# Top_Screw.net
KiCad netlist of a schematic drawn in EAGLE
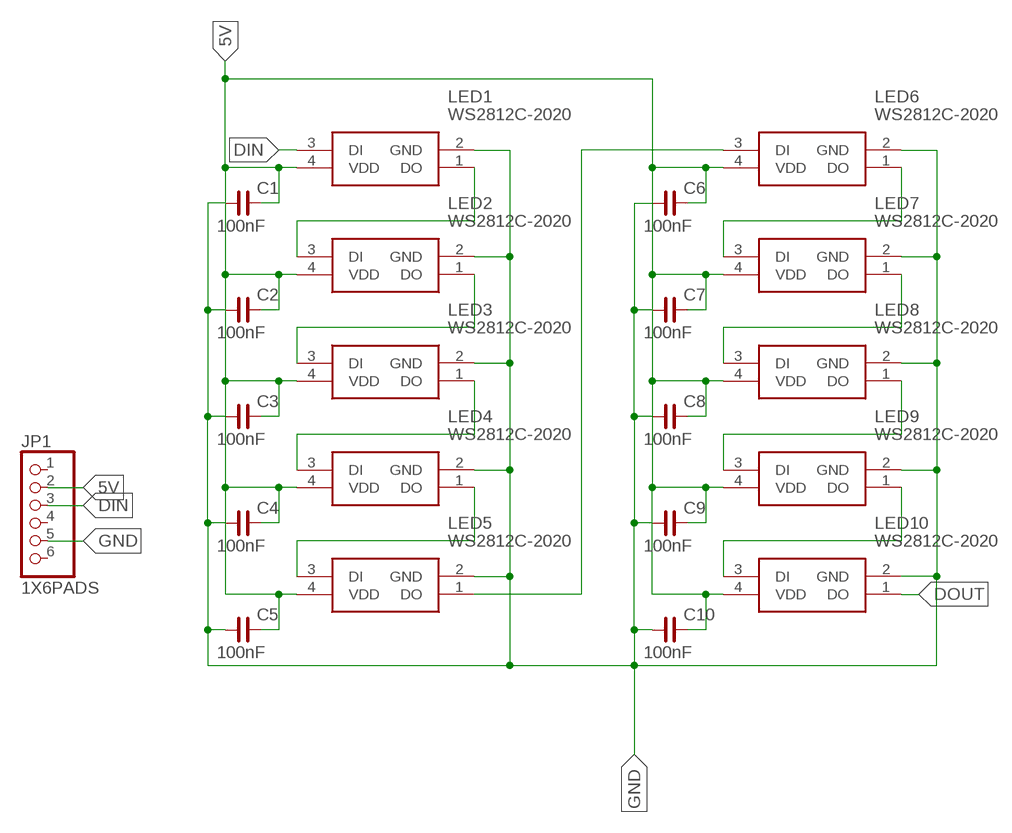
[diagram p0: schematic, sheet 1]

(export (version "E")
  (design (tool "Eeschema 10.0.6"))
  (components
    (comp (ref "C1")
      (value "100nF")
      (footprint "eagle-import:C0402")
      (libsource (lib "eagle-import") (part "C_0402"))
    )
    (comp (ref "C2")
      (value "100nF")
      (footprint "eagle-import:C0402")
      (libsource (lib "eagle-import") (part "C_0402"))
    )
    (comp (ref "C3")
      (value "100nF")
      (footprint "eagle-import:C0402")
      (libsource (lib "eagle-import") (part "C_0402"))
    )
    (comp (ref "C4")
      (value "100nF")
      (footprint "eagle-import:C0402")
      (libsource (lib "eagle-import") (part "C_0402"))
    )
    (comp (ref "C5")
      (value "100nF")
      (footprint "eagle-import:C0402")
      (libsource (lib "eagle-import") (part "C_0402"))
    )
    (comp (ref "C6")
      (value "100nF")
      (footprint "eagle-import:C0402")
      (libsource (lib "eagle-import") (part "C_0402"))
    )
    (comp (ref "C7")
      (value "100nF")
      (footprint "eagle-import:C0402")
      (libsource (lib "eagle-import") (part "C_0402"))
    )
    (comp (ref "C8")
      (value "100nF")
      (footprint "eagle-import:C0402")
      (libsource (lib "eagle-import") (part "C_0402"))
    )
    (comp (ref "C9")
      (value "100nF")
      (footprint "eagle-import:C0402")
      (libsource (lib "eagle-import") (part "C_0402"))
    )
    (comp (ref "C10")
      (value "100nF")
      (footprint "eagle-import:C0402")
      (libsource (lib "eagle-import") (part "C_0402"))
    )
    (comp (ref "JP1")
      (value "1X6PADS")
      (footprint "eagle-import:1X6PADS")
      (libsource (lib "eagle-import") (part "1X6PADS"))
    )
    (comp (ref "LED1")
      (value "WS2812C-2020")
      (footprint "eagle-import:WS2812C2020")
      (libsource (lib "eagle-import") (part "WS2812C-2020"))
    )
    (comp (ref "LED2")
      (value "WS2812C-2020")
      (footprint "eagle-import:WS2812C2020")
      (libsource (lib "eagle-import") (part "WS2812C-2020"))
    )
    (comp (ref "LED3")
      (value "WS2812C-2020")
      (footprint "eagle-import:WS2812C2020")
      (libsource (lib "eagle-import") (part "WS2812C-2020"))
    )
    (comp (ref "LED4")
      (value "WS2812C-2020")
      (footprint "eagle-import:WS2812C2020")
      (libsource (lib "eagle-import") (part "WS2812C-2020"))
    )
    (comp (ref "LED5")
      (value "WS2812C-2020")
      (footprint "eagle-import:WS2812C2020")
      (libsource (lib "eagle-import") (part "WS2812C-2020"))
    )
    (comp (ref "LED6")
      (value "WS2812C-2020")
      (footprint "eagle-import:WS2812C2020")
      (libsource (lib "eagle-import") (part "WS2812C-2020"))
    )
    (comp (ref "LED7")
      (value "WS2812C-2020")
      (footprint "eagle-import:WS2812C2020")
      (libsource (lib "eagle-import") (part "WS2812C-2020"))
    )
    (comp (ref "LED8")
      (value "WS2812C-2020")
      (footprint "eagle-import:WS2812C2020")
      (libsource (lib "eagle-import") (part "WS2812C-2020"))
    )
    (comp (ref "LED9")
      (value "WS2812C-2020")
      (footprint "eagle-import:WS2812C2020")
      (libsource (lib "eagle-import") (part "WS2812C-2020"))
    )
    (comp (ref "LED10")
      (value "WS2812C-2020")
      (footprint "eagle-import:WS2812C2020")
      (libsource (lib "eagle-import") (part "WS2812C-2020"))
    )
  )
  (nets
    (net (code "1") (name "5V") (class "Default")
      (node (ref "C1") (pin "2") (pinfunction "2_2") (pintype "passive"))
      (node (ref "C10") (pin "2") (pinfunction "2_2") (pintype "passive"))
      (node (ref "C2") (pin "2") (pinfunction "2_2") (pintype "passive"))
      (node (ref "C3") (pin "2") (pinfunction "2_2") (pintype "passive"))
      (node (ref "C4") (pin "2") (pinfunction "2_2") (pintype "passive"))
      (node (ref "C5") (pin "2") (pinfunction "2_2") (pintype "passive"))
      (node (ref "C6") (pin "2") (pinfunction "2_2") (pintype "passive"))
      (node (ref "C7") (pin "2") (pinfunction "2_2") (pintype "passive"))
      (node (ref "C8") (pin "2") (pinfunction "2_2") (pintype "passive"))
      (node (ref "C9") (pin "2") (pinfunction "2_2") (pintype "passive"))
      (node (ref "JP1") (pin "2") (pinfunction "2_2") (pintype "passive"))
      (node (ref "LED1") (pin "4") (pinfunction "VDD_4") (pintype "bidirectional"))
      (node (ref "LED10") (pin "4") (pinfunction "VDD_4") (pintype "bidirectional"))
      (node (ref "LED2") (pin "4") (pinfunction "VDD_4") (pintype "bidirectional"))
      (node (ref "LED3") (pin "4") (pinfunction "VDD_4") (pintype "bidirectional"))
      (node (ref "LED4") (pin "4") (pinfunction "VDD_4") (pintype "bidirectional"))
      (node (ref "LED5") (pin "4") (pinfunction "VDD_4") (pintype "bidirectional"))
      (node (ref "LED6") (pin "4") (pinfunction "VDD_4") (pintype "bidirectional"))
      (node (ref "LED7") (pin "4") (pinfunction "VDD_4") (pintype "bidirectional"))
      (node (ref "LED8") (pin "4") (pinfunction "VDD_4") (pintype "bidirectional"))
      (node (ref "LED9") (pin "4") (pinfunction "VDD_4") (pintype "bidirectional"))
    )
    (net (code "2") (name "DIN") (class "Default")
      (node (ref "JP1") (pin "3") (pinfunction "3_3") (pintype "passive"))
      (node (ref "LED1") (pin "3") (pinfunction "DI_3") (pintype "bidirectional"))
    )
    (net (code "3") (name "DOUT") (class "Default")
      (node (ref "LED10") (pin "1") (pinfunction "DO_1") (pintype "bidirectional"))
    )
    (net (code "4") (name "GND") (class "Default")
      (node (ref "C1") (pin "1") (pinfunction "1_1") (pintype "passive"))
      (node (ref "C10") (pin "1") (pinfunction "1_1") (pintype "passive"))
      (node (ref "C2") (pin "1") (pinfunction "1_1") (pintype "passive"))
      (node (ref "C3") (pin "1") (pinfunction "1_1") (pintype "passive"))
      (node (ref "C4") (pin "1") (pinfunction "1_1") (pintype "passive"))
      (node (ref "C5") (pin "1") (pinfunction "1_1") (pintype "passive"))
      (node (ref "C6") (pin "1") (pinfunction "1_1") (pintype "passive"))
      (node (ref "C7") (pin "1") (pinfunction "1_1") (pintype "passive"))
      (node (ref "C8") (pin "1") (pinfunction "1_1") (pintype "passive"))
      (node (ref "C9") (pin "1") (pinfunction "1_1") (pintype "passive"))
      (node (ref "JP1") (pin "5") (pinfunction "5_5") (pintype "passive"))
      (node (ref "LED1") (pin "2") (pinfunction "GND_2") (pintype "bidirectional"))
      (node (ref "LED10") (pin "2") (pinfunction "GND_2") (pintype "bidirectional"))
      (node (ref "LED2") (pin "2") (pinfunction "GND_2") (pintype "bidirectional"))
      (node (ref "LED3") (pin "2") (pinfunction "GND_2") (pintype "bidirectional"))
      (node (ref "LED4") (pin "2") (pinfunction "GND_2") (pintype "bidirectional"))
      (node (ref "LED5") (pin "2") (pinfunction "GND_2") (pintype "bidirectional"))
      (node (ref "LED6") (pin "2") (pinfunction "GND_2") (pintype "bidirectional"))
      (node (ref "LED7") (pin "2") (pinfunction "GND_2") (pintype "bidirectional"))
      (node (ref "LED8") (pin "2") (pinfunction "GND_2") (pintype "bidirectional"))
      (node (ref "LED9") (pin "2") (pinfunction "GND_2") (pintype "bidirectional"))
    )
    (net (code "5") (name "Net-(LED1-DO)") (class "Default")
      (node (ref "LED1") (pin "1") (pinfunction "DO_1") (pintype "bidirectional"))
      (node (ref "LED2") (pin "3") (pinfunction "DI_3") (pintype "bidirectional"))
    )
    (net (code "6") (name "Net-(LED2-DO)") (class "Default")
      (node (ref "LED2") (pin "1") (pinfunction "DO_1") (pintype "bidirectional"))
      (node (ref "LED3") (pin "3") (pinfunction "DI_3") (pintype "bidirectional"))
    )
    (net (code "7") (name "Net-(LED3-DO)") (class "Default")
      (node (ref "LED3") (pin "1") (pinfunction "DO_1") (pintype "bidirectional"))
      (node (ref "LED4") (pin "3") (pinfunction "DI_3") (pintype "bidirectional"))
    )
    (net (code "8") (name "Net-(LED4-DO)") (class "Default")
      (node (ref "LED4") (pin "1") (pinfunction "DO_1") (pintype "bidirectional"))
      (node (ref "LED5") (pin "3") (pinfunction "DI_3") (pintype "bidirectional"))
    )
    (net (code "9") (name "Net-(LED5-DO)") (class "Default")
      (node (ref "LED5") (pin "1") (pinfunction "DO_1") (pintype "bidirectional"))
      (node (ref "LED6") (pin "3") (pinfunction "DI_3") (pintype "bidirectional"))
    )
    (net (code "10") (name "Net-(LED6-DO)") (class "Default")
      (node (ref "LED6") (pin "1") (pinfunction "DO_1") (pintype "bidirectional"))
      (node (ref "LED7") (pin "3") (pinfunction "DI_3") (pintype "bidirectional"))
    )
    (net (code "11") (name "Net-(LED7-DO)") (class "Default")
      (node (ref "LED7") (pin "1") (pinfunction "DO_1") (pintype "bidirectional"))
      (node (ref "LED8") (pin "3") (pinfunction "DI_3") (pintype "bidirectional"))
    )
    (net (code "12") (name "Net-(LED8-DO)") (class "Default")
      (node (ref "LED8") (pin "1") (pinfunction "DO_1") (pintype "bidirectional"))
      (node (ref "LED9") (pin "3") (pinfunction "DI_3") (pintype "bidirectional"))
    )
    (net (code "13") (name "Net-(LED10-DI)") (class "Default")
      (node (ref "LED10") (pin "3") (pinfunction "DI_3") (pintype "bidirectional"))
      (node (ref "LED9") (pin "1") (pinfunction "DO_1") (pintype "bidirectional"))
    )
    (net (code "14") (name "unconnected-(JP1-Pad1)") (class "Default")
      (node (ref "JP1") (pin "1") (pinfunction "1_1") (pintype "passive"))
    )
    (net (code "15") (name "unconnected-(JP1-Pad4)") (class "Default")
      (node (ref "JP1") (pin "4") (pinfunction "4_4") (pintype "passive"))
    )
    (net (code "16") (name "unconnected-(JP1-Pad6)") (class "Default")
      (node (ref "JP1") (pin "6") (pinfunction "6_6") (pintype "passive"))
    )
  )
)
